# Fonte.net
KiCad netlist of a schematic drawn in EAGLE
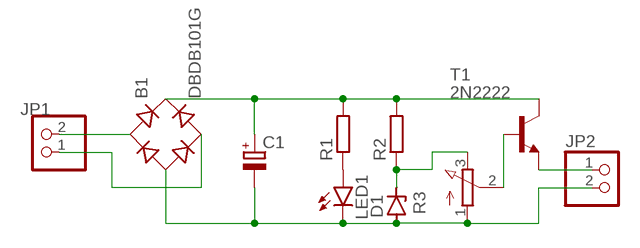
[diagram p0: schematic, sheet 1]

(export (version "E")
  (design (tool "Eeschema 10.0.6"))
  (components
    (comp (ref "B1")
      (value "DBDB101G")
      (footprint "eagle-import:DB")
      (libsource (lib "eagle-import") (part "DB?GDB101"))
    )
    (comp (ref "C1")
      (value "CPOL-EUE5-10.5")
      (footprint "eagle-import:E5-10,5")
      (libsource (lib "eagle-import") (part "CPOL-EUE5-10.5"))
    )
    (comp (ref "D1")
      (value "ZENER-DIODEDO41Z10")
      (footprint "eagle-import:DO41Z10")
      (libsource (lib "eagle-import") (part "ZENER-DIODEDO41Z10"))
    )
    (comp (ref "JP1")
      (value "PINHD-1X2")
      (footprint "eagle-import:1X02")
      (libsource (lib "eagle-import") (part "PINHD-1X2"))
    )
    (comp (ref "JP2")
      (value "PINHD-1X2")
      (footprint "eagle-import:1X02")
      (fields (field (name "SPICEPREFIX") "B"))
      (libsource (lib "eagle-import") (part "PINHD-1X2"))
    )
    (comp (ref "LED1")
      (value "LED5MM")
      (footprint "eagle-import:LED5MM")
      (libsource (lib "eagle-import") (part "LED5MM"))
    )
    (comp (ref "R1")
      (value "R-EU_0207/10")
      (footprint "eagle-import:0207_10")
      (libsource (lib "eagle-import") (part "R-EU_0207/10"))
    )
    (comp (ref "R2")
      (value "R-EU_0207/10")
      (footprint "eagle-import:0207_10")
      (libsource (lib "eagle-import") (part "R-EU_0207/10"))
    )
    (comp (ref "R3")
      (value "3RP/1610N")
      (footprint "eagle-import:3RP_1610N")
      (libsource (lib "eagle-import") (part "3RP/1610N"))
    )
    (comp (ref "T1")
      (value "2N2222")
      (footprint "eagle-import:TO18")
      (libsource (lib "eagle-import") (part "2N2222"))
    )
  )
  (nets
    (net (code "1") (name "Net-(B1-PadAC1)") (class "Default")
      (node (ref "B1") (pin "AC1") (pinfunction "AC1_AC1") (pintype "passive"))
      (node (ref "JP1") (pin "2") (pinfunction "2_2") (pintype "passive"))
    )
    (net (code "2") (name "Net-(B1-PadAC2)") (class "Default")
      (node (ref "B1") (pin "AC2") (pinfunction "AC2_AC2") (pintype "passive"))
      (node (ref "JP1") (pin "1") (pinfunction "1_1") (pintype "passive"))
    )
    (net (code "3") (name "Net-(LED1-C)") (class "Default")
      (node (ref "B1") (pin "-") (pinfunction "-_-") (pintype "passive"))
      (node (ref "C1") (pin "-") (pinfunction "-_-") (pintype "passive"))
      (node (ref "D1") (pin "A") (pinfunction "A_A") (pintype "passive"))
      (node (ref "JP2") (pin "2") (pinfunction "2_2") (pintype "passive"))
      (node (ref "LED1") (pin "K") (pinfunction "C_K") (pintype "passive"))
      (node (ref "R3") (pin "1") (pinfunction "A_1") (pintype "passive"))
    )
    (net (code "4") (name "Net-(LED1-PadA)") (class "Default")
      (node (ref "LED1") (pin "A") (pinfunction "A_A") (pintype "passive"))
      (node (ref "R1") (pin "1") (pinfunction "1_1") (pintype "passive"))
    )
    (net (code "5") (name "Net-(R3-E)") (class "Default")
      (node (ref "D1") (pin "C") (pinfunction "C_C") (pintype "passive"))
      (node (ref "R2") (pin "1") (pinfunction "1_1") (pintype "passive"))
      (node (ref "R3") (pin "3") (pinfunction "E_3") (pintype "passive"))
    )
    (net (code "6") (name "Net-(R3-S)") (class "Default")
      (node (ref "R3") (pin "2") (pinfunction "S_2") (pintype "passive"))
      (node (ref "T1") (pin "2") (pinfunction "B_2") (pintype "passive"))
    )
    (net (code "7") (name "Net-(T1-C)") (class "Default")
      (node (ref "B1") (pin "+") (pinfunction "+_+") (pintype "passive"))
      (node (ref "C1") (pin "+") (pinfunction "+_+") (pintype "passive"))
      (node (ref "R1") (pin "2") (pinfunction "2_2") (pintype "passive"))
      (node (ref "R2") (pin "2") (pinfunction "2_2") (pintype "passive"))
      (node (ref "T1") (pin "3") (pinfunction "C_3") (pintype "passive"))
    )
    (net (code "8") (name "Net-(T1-E)") (class "Default")
      (node (ref "JP2") (pin "1") (pinfunction "1_1") (pintype "passive"))
      (node (ref "T1") (pin "1") (pinfunction "E_1") (pintype "passive"))
    )
  )
)
